# simple-loop3.net
KiCad netlist of a schematic drawn in EAGLE
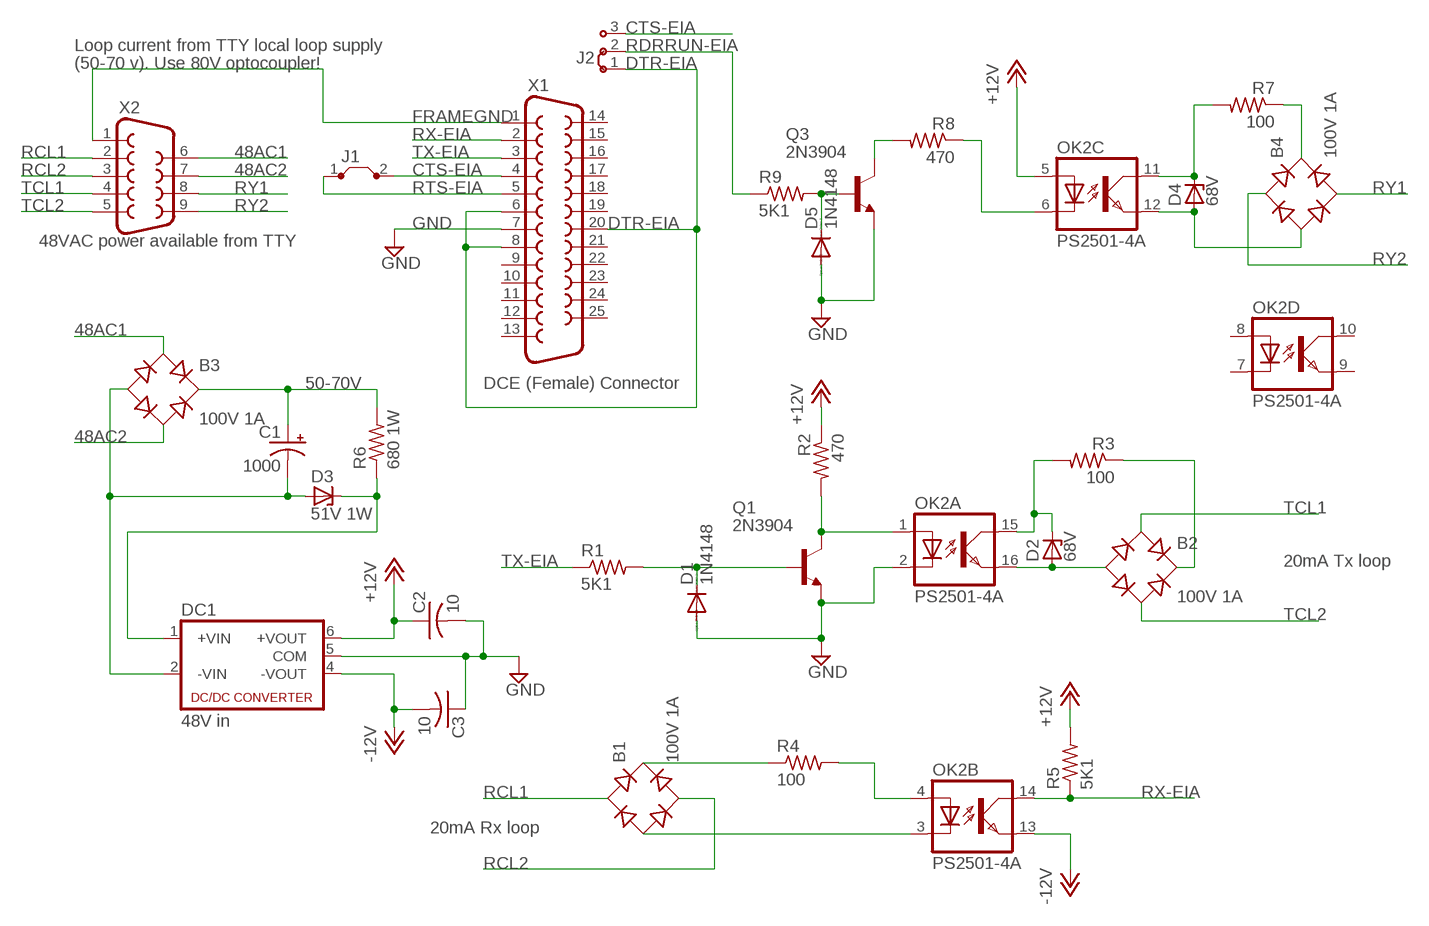
[diagram p0: schematic, sheet 1]

(export (version "E")
  (design (tool "Eeschema 10.0.6"))
  (components
    (comp (ref "B1")
      (value "100V 1A")
      (footprint "eagle-import:RB1A")
      (libsource (lib "eagle-import") (part "RB1A"))
    )
    (comp (ref "B2")
      (value "100V 1A")
      (footprint "eagle-import:RB1A")
      (libsource (lib "eagle-import") (part "RB1A"))
    )
    (comp (ref "B3")
      (value "100V 1A")
      (footprint "eagle-import:RB1A")
      (libsource (lib "eagle-import") (part "RB1A"))
    )
    (comp (ref "B4")
      (value "100V 1A")
      (footprint "eagle-import:RB1A")
      (libsource (lib "eagle-import") (part "RB1A"))
    )
    (comp (ref "C1")
      (value "1000")
      (footprint "eagle-import:E7,5-18")
      (libsource (lib "eagle-import") (part "CPOL-USE7.5-18"))
    )
    (comp (ref "C2")
      (value "10")
      (footprint "eagle-import:C025-025X050")
      (libsource (lib "eagle-import") (part "C-US025-025X050"))
    )
    (comp (ref "C3")
      (value "10")
      (footprint "eagle-import:C025-025X050")
      (libsource (lib "eagle-import") (part "C-US025-025X050"))
    )
    (comp (ref "D1")
      (value "1N4148")
      (footprint "eagle-import:DO35-10")
      (libsource (lib "eagle-import") (part "1N4148DO35-10"))
    )
    (comp (ref "D2")
      (value "68V")
      (footprint "eagle-import:DO41Z10")
      (libsource (lib "eagle-import") (part "ZENER-DIODEDO41Z10"))
    )
    (comp (ref "D3")
      (value "51V 1W")
      (footprint "eagle-import:DO41Z10")
      (libsource (lib "eagle-import") (part "ZENER-DIODEDO41Z10"))
    )
    (comp (ref "D4")
      (value "68V")
      (footprint "eagle-import:DO41Z10")
      (libsource (lib "eagle-import") (part "ZENER-DIODEDO41Z10"))
    )
    (comp (ref "D5")
      (value "1N4148")
      (footprint "eagle-import:DO35-10")
      (libsource (lib "eagle-import") (part "1N4148DO35-10"))
    )
    (comp (ref "DC1")
      (value "48V in")
      (footprint "eagle-import:NMA")
      (fields (field (name "MF") "C & D TECHNOLOGIES, INC") (field (name "MPN") "NMA0515SC"))
      (libsource (lib "eagle-import") (part "NMA"))
    )
    (comp (ref "J1")
      (value "J5MM")
      (footprint "eagle-import:05")
      (libsource (lib "eagle-import") (part "J5MM"))
    )
    (comp (ref "J2")
      (value "J2X5MM")
      (footprint "eagle-import:05C")
      (libsource (lib "eagle-import") (part "J2X5MM"))
    )
    (comp (ref "OK2")
      (value "PS2501-4A")
      (footprint "eagle-import:DIL16")
      (fields (field (name "MF") "VISHAY/TELEFUNKEN") (field (name "MPN") "ILQ1"))
      (libsource (lib "eagle-import") (part "ILQ1"))
    )
    (comp (ref "Q1")
      (value "2N3904")
      (footprint "eagle-import:TO92")
      (libsource (lib "eagle-import") (part "2N3904"))
    )
    (comp (ref "Q3")
      (value "2N3904")
      (footprint "eagle-import:TO92")
      (libsource (lib "eagle-import") (part "2N3904"))
    )
    (comp (ref "R1")
      (value "5K1")
      (footprint "eagle-import:0207_10")
      (libsource (lib "eagle-import") (part "R-US_0207/10"))
    )
    (comp (ref "R2")
      (value "470")
      (footprint "eagle-import:0207_10")
      (libsource (lib "eagle-import") (part "R-US_0207/10"))
    )
    (comp (ref "R3")
      (value "100")
      (footprint "eagle-import:0207_10")
      (libsource (lib "eagle-import") (part "R-US_0207/10"))
    )
    (comp (ref "R4")
      (value "100")
      (footprint "eagle-import:0207_10")
      (libsource (lib "eagle-import") (part "R-US_0207/10"))
    )
    (comp (ref "R5")
      (value "5K1")
      (footprint "eagle-import:0207_10")
      (libsource (lib "eagle-import") (part "R-US_0207/10"))
    )
    (comp (ref "R6")
      (value "680 1W")
      (footprint "eagle-import:0617_17")
      (libsource (lib "eagle-import") (part "R-US_0617/17"))
    )
    (comp (ref "R7")
      (value "100")
      (footprint "eagle-import:0207_10")
      (libsource (lib "eagle-import") (part "R-US_0207/10"))
    )
    (comp (ref "R8")
      (value "470")
      (footprint "eagle-import:0207_10")
      (libsource (lib "eagle-import") (part "R-US_0207/10"))
    )
    (comp (ref "R9")
      (value "5K1")
      (footprint "eagle-import:0207_10")
      (libsource (lib "eagle-import") (part "R-US_0207/10"))
    )
    (comp (ref "X1")
      (value "F25H")
      (footprint "eagle-import:F25H")
      (libsource (lib "eagle-import") (part "F25H"))
    )
    (comp (ref "X2")
      (value "F09H")
      (footprint "eagle-import:F09H")
      (libsource (lib "eagle-import") (part "F09H"))
    )
  )
  (nets
    (net (code "1") (name "+12V") (class "Default")
      (node (ref "C2") (pin "1") (pinfunction "1_1") (pintype "passive"))
      (node (ref "DC1") (pin "6") (pinfunction "+VOUT_6") (pintype "passive"))
      (node (ref "OK2") (pin "5") (pinfunction "A_5") (pintype "passive"))
      (node (ref "R2") (pin "1") (pinfunction "1_1") (pintype "passive"))
      (node (ref "R5") (pin "2") (pinfunction "2_2") (pintype "passive"))
    )
    (net (code "2") (name "-12V") (class "Default")
      (node (ref "C3") (pin "2") (pinfunction "2_2") (pintype "passive"))
      (node (ref "DC1") (pin "4") (pinfunction "-VOUT_4") (pintype "passive"))
      (node (ref "OK2") (pin "13") (pinfunction "EMIT_13") (pintype "passive"))
    )
    (net (code "3") (name "/48AC1") (class "Default")
      (node (ref "B3") (pin "AC1") (pinfunction "AC1_AC1") (pintype "passive"))
      (node (ref "X2") (pin "6") (pinfunction "6_6") (pintype "passive"))
    )
    (net (code "4") (name "/48AC2") (class "Default")
      (node (ref "B3") (pin "AC2") (pinfunction "AC2_AC2") (pintype "passive"))
      (node (ref "X2") (pin "7") (pinfunction "7_7") (pintype "passive"))
    )
    (net (code "5") (name "/50-70V") (class "Default")
      (node (ref "B3") (pin "+") (pinfunction "+_+") (pintype "passive"))
      (node (ref "C1") (pin "+") (pinfunction "+_+") (pintype "passive"))
      (node (ref "R6") (pin "2") (pinfunction "2_2") (pintype "passive"))
    )
    (net (code "6") (name "/CTS-EIA") (class "Default")
      (node (ref "J1") (pin "2") (pinfunction "2_2") (pintype "passive"))
      (node (ref "J2") (pin "3") (pinfunction "3_3") (pintype "passive"))
      (node (ref "X1") (pin "4") (pinfunction "4_4") (pintype "passive"))
    )
    (net (code "7") (name "/DTR-EIA") (class "Default")
      (node (ref "J2") (pin "1") (pinfunction "1_1") (pintype "passive"))
      (node (ref "X1") (pin "20") (pinfunction "20_20") (pintype "passive"))
      (node (ref "X1") (pin "6") (pinfunction "6_6") (pintype "passive"))
      (node (ref "X1") (pin "8") (pinfunction "8_8") (pintype "passive"))
    )
    (net (code "8") (name "/FRAMEGND") (class "Default")
      (node (ref "X1") (pin "1") (pinfunction "1_1") (pintype "passive"))
      (node (ref "X2") (pin "1") (pinfunction "1_1") (pintype "passive"))
    )
    (net (code "9") (name "/RCL1") (class "Default")
      (node (ref "B1") (pin "AC1") (pinfunction "AC1_AC1") (pintype "passive"))
      (node (ref "X2") (pin "2") (pinfunction "2_2") (pintype "passive"))
    )
    (net (code "10") (name "/RCL2") (class "Default")
      (node (ref "B1") (pin "AC2") (pinfunction "AC2_AC2") (pintype "passive"))
      (node (ref "X2") (pin "3") (pinfunction "3_3") (pintype "passive"))
    )
    (net (code "11") (name "/RDRRUN-EIA") (class "Default")
      (node (ref "J2") (pin "2") (pinfunction "2_2") (pintype "passive"))
      (node (ref "R9") (pin "1") (pinfunction "1_1") (pintype "passive"))
    )
    (net (code "12") (name "/RTS-EIA") (class "Default")
      (node (ref "J1") (pin "1") (pinfunction "1_1") (pintype "passive"))
      (node (ref "X1") (pin "5") (pinfunction "5_5") (pintype "passive"))
    )
    (net (code "13") (name "/RX-EIA") (class "Default")
      (node (ref "OK2") (pin "14") (pinfunction "COL_14") (pintype "passive"))
      (node (ref "R5") (pin "1") (pinfunction "1_1") (pintype "passive"))
      (node (ref "X1") (pin "2") (pinfunction "2_2") (pintype "passive"))
    )
    (net (code "14") (name "/RY1") (class "Default")
      (node (ref "B4") (pin "AC2") (pinfunction "AC2_AC2") (pintype "passive"))
      (node (ref "X2") (pin "8") (pinfunction "8_8") (pintype "passive"))
    )
    (net (code "15") (name "/RY2") (class "Default")
      (node (ref "B4") (pin "AC1") (pinfunction "AC1_AC1") (pintype "passive"))
      (node (ref "X2") (pin "9") (pinfunction "9_9") (pintype "passive"))
    )
    (net (code "16") (name "/TCL1") (class "Default")
      (node (ref "B2") (pin "AC1") (pinfunction "AC1_AC1") (pintype "passive"))
      (node (ref "X2") (pin "4") (pinfunction "4_4") (pintype "passive"))
    )
    (net (code "17") (name "/TCL2") (class "Default")
      (node (ref "B2") (pin "AC2") (pinfunction "AC2_AC2") (pintype "passive"))
      (node (ref "X2") (pin "5") (pinfunction "5_5") (pintype "passive"))
    )
    (net (code "18") (name "/TX-EIA") (class "Default")
      (node (ref "R1") (pin "1") (pinfunction "1_1") (pintype "passive"))
      (node (ref "X1") (pin "3") (pinfunction "3_3") (pintype "passive"))
    )
    (net (code "19") (name "GND") (class "Default")
      (node (ref "C2") (pin "2") (pinfunction "2_2") (pintype "passive"))
      (node (ref "C3") (pin "1") (pinfunction "1_1") (pintype "passive"))
      (node (ref "D1") (pin "A") (pinfunction "A_A") (pintype "passive"))
      (node (ref "D5") (pin "A") (pinfunction "A_A") (pintype "passive"))
      (node (ref "DC1") (pin "5") (pinfunction "COM_5") (pintype "passive"))
      (node (ref "OK2") (pin "2") (pinfunction "C_2") (pintype "passive"))
      (node (ref "Q1") (pin "3") (pinfunction "E_3") (pintype "passive"))
      (node (ref "Q3") (pin "3") (pinfunction "E_3") (pintype "passive"))
      (node (ref "X1") (pin "7") (pinfunction "7_7") (pintype "passive"))
    )
    (net (code "20") (name "Net-(B1-Pad+)") (class "Default")
      (node (ref "B1") (pin "+") (pinfunction "+_+") (pintype "passive"))
      (node (ref "R4") (pin "1") (pinfunction "1_1") (pintype "passive"))
    )
    (net (code "21") (name "Net-(B2-Pad+)") (class "Default")
      (node (ref "B2") (pin "+") (pinfunction "+_+") (pintype "passive"))
      (node (ref "R3") (pin "1") (pinfunction "1_1") (pintype "passive"))
    )
    (net (code "22") (name "Net-(B4-Pad+)") (class "Default")
      (node (ref "B4") (pin "+") (pinfunction "+_+") (pintype "passive"))
      (node (ref "R7") (pin "1") (pinfunction "1_1") (pintype "passive"))
    )
    (net (code "23") (name "Net-(DC1-+VIN)") (class "Default")
      (node (ref "D3") (pin "C") (pinfunction "C_C") (pintype "passive"))
      (node (ref "DC1") (pin "1") (pinfunction "+VIN_1") (pintype "passive"))
      (node (ref "R6") (pin "1") (pinfunction "1_1") (pintype "passive"))
    )
    (net (code "24") (name "Net-(DC1--VIN)") (class "Default")
      (node (ref "B3") (pin "-") (pinfunction "-_-") (pintype "passive"))
      (node (ref "C1") (pin "-") (pinfunction "-_-") (pintype "passive"))
      (node (ref "D3") (pin "A") (pinfunction "A_A") (pintype "passive"))
      (node (ref "DC1") (pin "2") (pinfunction "-VIN_2") (pintype "passive"))
    )
    (net (code "25") (name "Net-(OK2A-A)") (class "Default")
      (node (ref "OK2") (pin "1") (pinfunction "A_1") (pintype "passive"))
      (node (ref "Q1") (pin "1") (pinfunction "C_1") (pintype "passive"))
      (node (ref "R2") (pin "2") (pinfunction "2_2") (pintype "passive"))
    )
    (net (code "26") (name "Net-(OK2A-COL)") (class "Default")
      (node (ref "D2") (pin "C") (pinfunction "C_C") (pintype "passive"))
      (node (ref "OK2") (pin "15") (pinfunction "COL_15") (pintype "passive"))
      (node (ref "R3") (pin "2") (pinfunction "2_2") (pintype "passive"))
    )
    (net (code "27") (name "Net-(OK2A-EMIT)") (class "Default")
      (node (ref "B2") (pin "-") (pinfunction "-_-") (pintype "passive"))
      (node (ref "D2") (pin "A") (pinfunction "A_A") (pintype "passive"))
      (node (ref "OK2") (pin "16") (pinfunction "EMIT_16") (pintype "passive"))
    )
    (net (code "28") (name "Net-(OK2B-A)") (class "Default")
      (node (ref "OK2") (pin "4") (pinfunction "A_4") (pintype "passive"))
      (node (ref "R4") (pin "2") (pinfunction "2_2") (pintype "passive"))
    )
    (net (code "29") (name "Net-(OK2B-C)") (class "Default")
      (node (ref "B1") (pin "-") (pinfunction "-_-") (pintype "passive"))
      (node (ref "OK2") (pin "3") (pinfunction "C_3") (pintype "passive"))
    )
    (net (code "30") (name "Net-(OK2C-C)") (class "Default")
      (node (ref "OK2") (pin "6") (pinfunction "C_6") (pintype "passive"))
      (node (ref "R8") (pin "1") (pinfunction "1_1") (pintype "passive"))
    )
    (net (code "31") (name "Net-(OK2C-COL)") (class "Default")
      (node (ref "D4") (pin "C") (pinfunction "C_C") (pintype "passive"))
      (node (ref "OK2") (pin "11") (pinfunction "COL_11") (pintype "passive"))
      (node (ref "R7") (pin "2") (pinfunction "2_2") (pintype "passive"))
    )
    (net (code "32") (name "Net-(OK2C-EMIT)") (class "Default")
      (node (ref "B4") (pin "-") (pinfunction "-_-") (pintype "passive"))
      (node (ref "D4") (pin "A") (pinfunction "A_A") (pintype "passive"))
      (node (ref "OK2") (pin "12") (pinfunction "EMIT_12") (pintype "passive"))
    )
    (net (code "33") (name "Net-(Q1-B)") (class "Default")
      (node (ref "D1") (pin "C") (pinfunction "C_C") (pintype "passive"))
      (node (ref "Q1") (pin "2") (pinfunction "B_2") (pintype "passive"))
      (node (ref "R1") (pin "2") (pinfunction "2_2") (pintype "passive"))
    )
    (net (code "34") (name "Net-(Q3-B)") (class "Default")
      (node (ref "D5") (pin "C") (pinfunction "C_C") (pintype "passive"))
      (node (ref "Q3") (pin "2") (pinfunction "B_2") (pintype "passive"))
      (node (ref "R9") (pin "2") (pinfunction "2_2") (pintype "passive"))
    )
    (net (code "35") (name "Net-(Q3-C)") (class "Default")
      (node (ref "Q3") (pin "1") (pinfunction "C_1") (pintype "passive"))
      (node (ref "R8") (pin "2") (pinfunction "2_2") (pintype "passive"))
    )
    (net (code "36") (name "unconnected-(OK2D-A-Pad8)") (class "Default")
      (node (ref "OK2") (pin "8") (pinfunction "A_8") (pintype "passive"))
    )
    (net (code "37") (name "unconnected-(OK2D-C-Pad7)") (class "Default")
      (node (ref "OK2") (pin "7") (pinfunction "C_7") (pintype "passive"))
    )
    (net (code "38") (name "unconnected-(OK2D-COL-Pad10)") (class "Default")
      (node (ref "OK2") (pin "10") (pinfunction "COL_10") (pintype "passive"))
    )
    (net (code "39") (name "unconnected-(OK2D-EMIT-Pad9)") (class "Default")
      (node (ref "OK2") (pin "9") (pinfunction "EMIT_9") (pintype "passive"))
    )
    (net (code "40") (name "unconnected-(X1-Pad9)") (class "Default")
      (node (ref "X1") (pin "9") (pinfunction "9_9") (pintype "passive"))
    )
    (net (code "41") (name "unconnected-(X1-Pad10)") (class "Default")
      (node (ref "X1") (pin "10") (pinfunction "10_10") (pintype "passive"))
    )
    (net (code "42") (name "unconnected-(X1-Pad11)") (class "Default")
      (node (ref "X1") (pin "11") (pinfunction "11_11") (pintype "passive"))
    )
    (net (code "43") (name "unconnected-(X1-Pad12)") (class "Default")
      (node (ref "X1") (pin "12") (pinfunction "12_12") (pintype "passive"))
    )
    (net (code "44") (name "unconnected-(X1-Pad13)") (class "Default")
      (node (ref "X1") (pin "13") (pinfunction "13_13") (pintype "passive"))
    )
    (net (code "45") (name "unconnected-(X1-Pad14)") (class "Default")
      (node (ref "X1") (pin "14") (pinfunction "14_14") (pintype "passive"))
    )
    (net (code "46") (name "unconnected-(X1-Pad15)") (class "Default")
      (node (ref "X1") (pin "15") (pinfunction "15_15") (pintype "passive"))
    )
    (net (code "47") (name "unconnected-(X1-Pad16)") (class "Default")
      (node (ref "X1") (pin "16") (pinfunction "16_16") (pintype "passive"))
    )
    (net (code "48") (name "unconnected-(X1-Pad17)") (class "Default")
      (node (ref "X1") (pin "17") (pinfunction "17_17") (pintype "passive"))
    )
    (net (code "49") (name "unconnected-(X1-Pad18)") (class "Default")
      (node (ref "X1") (pin "18") (pinfunction "18_18") (pintype "passive"))
    )
    (net (code "50") (name "unconnected-(X1-Pad19)") (class "Default")
      (node (ref "X1") (pin "19") (pinfunction "19_19") (pintype "passive"))
    )
    (net (code "51") (name "unconnected-(X1-Pad21)") (class "Default")
      (node (ref "X1") (pin "21") (pinfunction "21_21") (pintype "passive"))
    )
    (net (code "52") (name "unconnected-(X1-Pad22)") (class "Default")
      (node (ref "X1") (pin "22") (pinfunction "22_22") (pintype "passive"))
    )
    (net (code "53") (name "unconnected-(X1-Pad23)") (class "Default")
      (node (ref "X1") (pin "23") (pinfunction "23_23") (pintype "passive"))
    )
    (net (code "54") (name "unconnected-(X1-Pad24)") (class "Default")
      (node (ref "X1") (pin "24") (pinfunction "24_24") (pintype "passive"))
    )
    (net (code "55") (name "unconnected-(X1-Pad25)") (class "Default")
      (node (ref "X1") (pin "25") (pinfunction "25_25") (pintype "passive"))
    )
  )
)
